# 31_STM32.net
KiCad netlist of a schematic drawn in Altium Designer
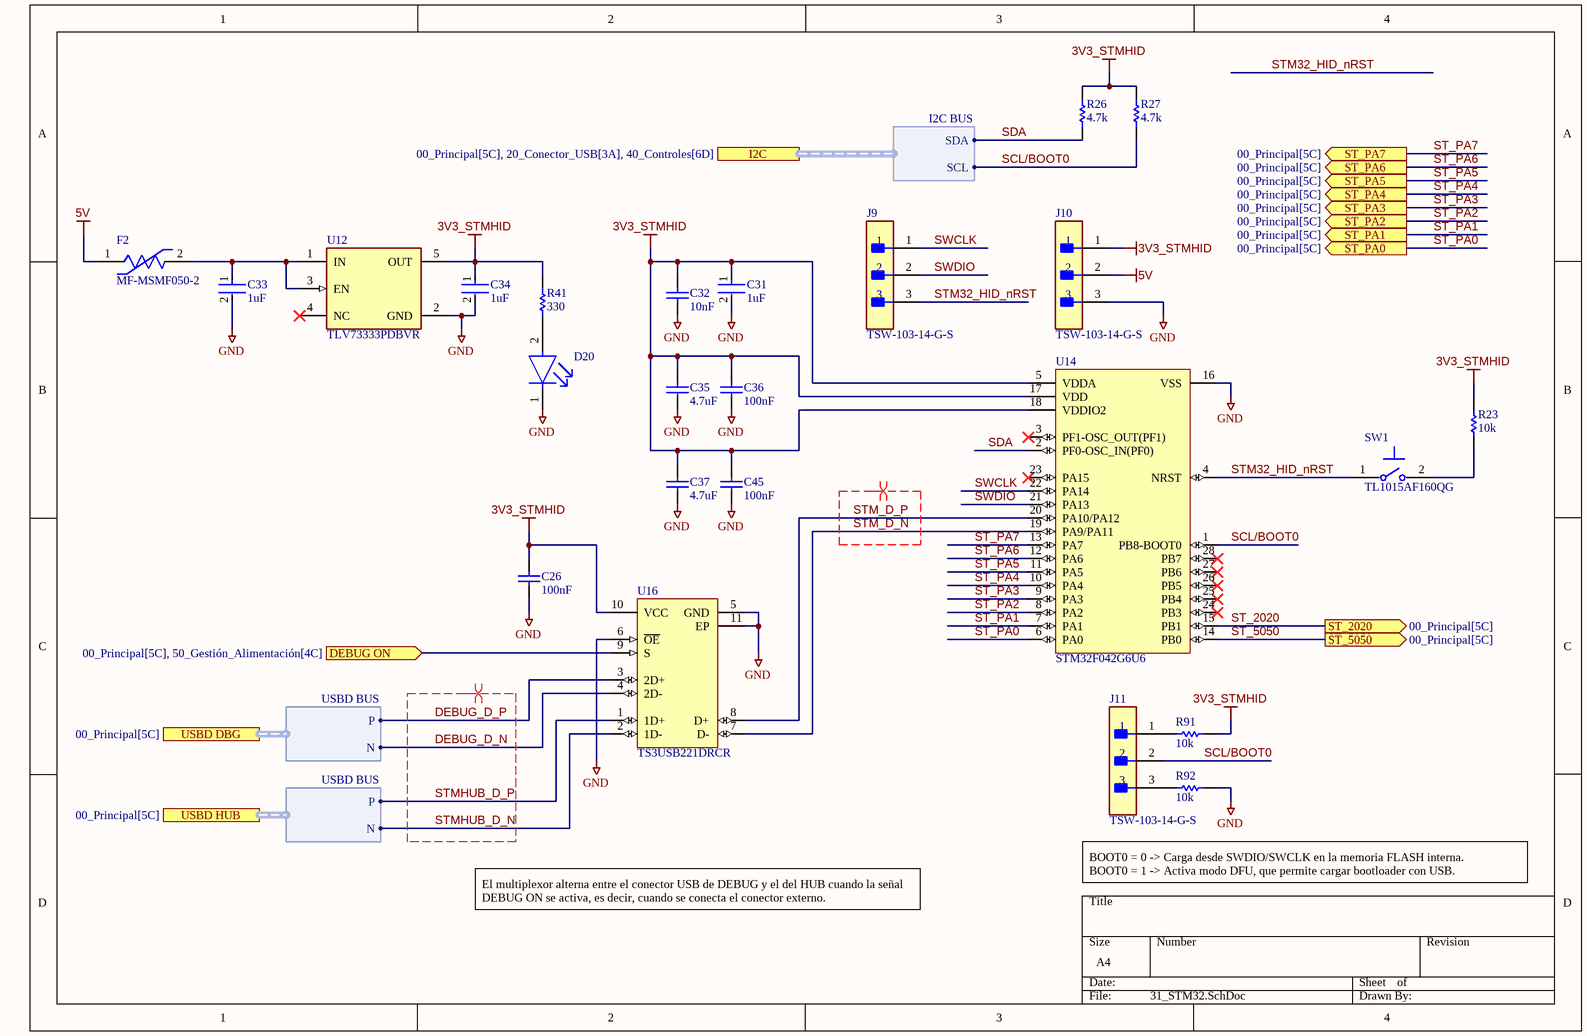
[diagram p0: 31_STM32.SchDoc]

(export (version "E")
  (design (tool "Eeschema 10.0.6"))
  (components
    (comp (ref "C26")
      (value "100nF")
      (footprint "CAPC1005X55X25NL05T05")
      (fields (field (name "MANUFACTURER") "Vitramon") (field (name "PART NUMBER") "VJ0402Y104KXJCW1BC"))
      (libsource (lib "Altium Content Vault") (part "CAP"))
    )
    (comp (ref "C31")
      (value "1uF")
      (footprint "FP-C0402C-BB-IPC_B")
      (description "CAP CER 1UF 16V X5R 0402")
      (fields (field (name "TOLERANCE") "10%"))
      (libsource (lib "Altium Content Vault") (part "b4654b650e69147ec39a6b967a45e02"))
    )
    (comp (ref "C32")
      (value "10nF")
      (footprint "CAPC1005X55X25ML05T05")
      (fields (field (name "PART NUMBER") "VJ0402Y103KXJCW1BC") (field (name "MANUFACTURER") "Vitramon"))
      (libsource (lib "Altium Content Vault") (part "CAP"))
    )
    (comp (ref "C33")
      (value "1uF")
      (footprint "FP-C0402C-BB-IPC_B")
      (description "CAP CER 1UF 16V X5R 0402")
      (fields (field (name "TOLERANCE") "10%"))
      (libsource (lib "Altium Content Vault") (part "b4654b650e69147ec39a6b967a45e02"))
    )
    (comp (ref "C34")
      (value "1uF")
      (footprint "FP-C0402C-BB-IPC_B")
      (description "CAP CER 1UF 16V X5R 0402")
      (fields (field (name "TOLERANCE") "10%"))
      (libsource (lib "Altium Content Vault") (part "b4654b650e69147ec39a6b967a45e02"))
    )
    (comp (ref "C35")
      (value "4.7uF")
      (footprint "CAPC1005X71X25NL10T15")
      (fields
        (field (name "PART NUMBER") "0402ZD475MAT2A")
        (field (name "MANUFACTURER") "AVX Interconnect / Elco")
      )
      (libsource (lib "Altium Content Vault") (part "CAP"))
    )
    (comp (ref "C36")
      (value "100nF")
      (footprint "CAPC1005X55X25NL05T05")
      (fields (field (name "MANUFACTURER") "Vitramon") (field (name "PART NUMBER") "VJ0402Y104KXJCW1BC"))
      (libsource (lib "Altium Content Vault") (part "CAP"))
    )
    (comp (ref "C37")
      (value "4.7uF")
      (footprint "CAPC1005X71X25NL10T15")
      (fields
        (field (name "PART NUMBER") "0402ZD475MAT2A")
        (field (name "MANUFACTURER") "AVX Interconnect / Elco")
      )
      (libsource (lib "Altium Content Vault") (part "CAP"))
    )
    (comp (ref "C45")
      (value "100nF")
      (footprint "CAPC1005X55X25NL05T05")
      (fields (field (name "MANUFACTURER") "Vitramon") (field (name "PART NUMBER") "VJ0402Y104KXJCW1BC"))
      (libsource (lib "Altium Content Vault") (part "CAP"))
    )
    (comp (ref "D20")
      (value "APHD1608LZGCK")
      (footprint "FP-APHD1608LZGCK-MFG")
      (description "LED GREEN CLEAR 1608 SMD")
      (libsource (lib "Altium Content Vault") (part "8706943c75ba83719d021d2fdc84c58"))
    )
    (comp (ref "F2")
      (value "MF-MSMF050-2")
      (footprint "FP-MF-MSMF050-2-MFG")
      (description "PTC RESET FUSE 15V 500MA 1812")
      (fields
        (field (name "MANUFACTURER") "Bourns")
        (field (name "OCTOPART") "https://octopart.com/mf-msmf050-2-bourns-28047")
      )
      (libsource (lib "Altium Content Vault") (part "fc31388045fc42ab786d6d00b506e9f"))
    )
    (comp (ref "J9")
      (value "TSW-103-14-G-S")
      (footprint "FP-TSW-103-14-G-S-MFG")
      (description "CONN HEADER VERT 3POS 2.54MM")
      (libsource (lib "Altium Content Vault") (part "cd3439d6ef35ae5d9b27ec4fdd3e828"))
    )
    (comp (ref "J10")
      (value "TSW-103-14-G-S")
      (footprint "FP-TSW-103-14-G-S-MFG")
      (description "CONN HEADER VERT 3POS 2.54MM")
      (libsource (lib "Altium Content Vault") (part "cd3439d6ef35ae5d9b27ec4fdd3e828"))
    )
    (comp (ref "J11")
      (value "TSW-103-14-G-S")
      (footprint "FP-TSW-103-14-G-S-MFG")
      (description "CONN HEADER VERT 3POS 2.54MM")
      (libsource (lib "Altium Content Vault") (part "cd3439d6ef35ae5d9b27ec4fdd3e828"))
    )
    (comp (ref "R23")
      (value "10k")
      (footprint "RESC1005X40X25ML05T05")
      (fields (field (name "MANUFACTURER") "Panasonic") (field (name "PART NUMBER") "ERJ-2RHD1002X"))
      (libsource (lib "Altium Content Vault") (part "RES"))
    )
    (comp (ref "R26")
      (value "4.7k")
      (footprint "RESC1005X40X25ML05T10")
      (fields (field (name "MANUFACTURER") "Panasonic") (field (name "PART NUMBER") "ERJ-S02F4701X"))
      (libsource (lib "Altium Content Vault") (part "RES"))
    )
    (comp (ref "R27")
      (value "4.7k")
      (footprint "RESC1005X40X25ML05T10")
      (fields (field (name "MANUFACTURER") "Panasonic") (field (name "PART NUMBER") "ERJ-S02F4701X"))
      (libsource (lib "Altium Content Vault") (part "RES"))
    )
    (comp (ref "R41")
      (value "330")
      (footprint "RESC1005X40X25NL10T10")
      (fields (field (name "MANUFACTURER") "Panasonic") (field (name "PART NUMBER") "ERA2AEB331X"))
      (libsource (lib "Altium Content Vault") (part "RES"))
    )
    (comp (ref "R91")
      (value "10k")
      (footprint "RESC1005X40X25ML05T05")
      (fields (field (name "MANUFACTURER") "Panasonic") (field (name "PART NUMBER") "ERJ-2RHD1002X"))
      (libsource (lib "Altium Content Vault") (part "RES"))
    )
    (comp (ref "R92")
      (value "10k")
      (footprint "RESC1005X40X25ML05T05")
      (fields (field (name "MANUFACTURER") "Panasonic") (field (name "PART NUMBER") "ERJ-2RHD1002X"))
      (libsource (lib "Altium Content Vault") (part "RES"))
    )
    (comp (ref "SW1")
      (value "TL1015AF160QG")
      (footprint "FP-TL1015AF160QG-MFG")
      (description "SWITCH TACTILE SPST-NO 0.05A 12V")
      (libsource (lib "Altium Content Vault") (part "2041f8efb62e6aaa548c9fd35e2c2f1"))
    )
    (comp (ref "U12")
      (value "TLV73333PDBVR")
      (footprint "FP-DBV0005A-MFG")
      (description "IC REG LINEAR 3.3V 300MA SOT23-5")
      (fields
        (field (name "MANUFACTURER") "Texas Instruments")
        (field (name "OCTOPART") "https://octopart.com/tlv73333pdbvr-texas+instruments-51080890")
      )
      (libsource (lib "Altium Content Vault") (part "10cdd6a861ce8db355dac0efc8b397e"))
    )
    (comp (ref "U14")
      (value "STM32F042G6U6")
      (footprint "STM-UFQFPN28_V")
      (fields (field (name "MANUFACTURER") "STMicroelectronics"))
      (libsource (lib "Altium Content Vault") (part "MC-ARM-STM32F042-UFQFPN28"))
    )
    (comp (ref "U16")
      (value "TS3USB221DRCR")
      (footprint "DRC0010J_V")
      (fields (field (name "MANUFACTURER") "Texas Instruments"))
      (libsource (lib "Altium Content Vault") (part "TI-TS3USB221-SON_DRC-10"))
    )
  )
  (nets
    (net (code "4") (name "/DEBUG ON") (class "Default")
      (node (ref "U16") (pin "9") (pinfunction "S_9") (pintype "input"))
    )
    (net (code "5") (name "/DEBUG_D_N") (class "Default")
      (node (ref "U16") (pin "4") (pinfunction "2D-_4") (pintype "bidirectional"))
    )
    (net (code "6") (name "/DEBUG_D_P") (class "Default")
      (node (ref "U16") (pin "3") (pinfunction "2D+_3") (pintype "bidirectional"))
    )
    (net (code "7") (name "/SCL{slash}BOOT0") (class "Default")
      (node (ref "J11") (pin "2") (pinfunction "2_2") (pintype "passive"))
      (node (ref "R27") (pin "1") (pinfunction "1_1") (pintype "passive"))
      (node (ref "U14") (pin "1") (pinfunction "PB8-BOOT0_1") (pintype "bidirectional"))
    )
    (net (code "8") (name "/SDA") (class "Default")
      (node (ref "R26") (pin "1") (pinfunction "1_1") (pintype "passive"))
      (node (ref "U14") (pin "2") (pinfunction "PF0-OSC_IN(PF0)_2") (pintype "bidirectional"))
    )
    (net (code "9") (name "/STM32_HID_nRST") (class "Default")
      (node (ref "J9") (pin "3") (pinfunction "3_3") (pintype "passive"))
      (node (ref "SW1") (pin "1") (pinfunction "1_1") (pintype "passive"))
      (node (ref "U14") (pin "4") (pinfunction "NRST_4") (pintype "bidirectional"))
    )
    (net (code "10") (name "/STMHUB_D_N") (class "Default")
      (node (ref "U16") (pin "2") (pinfunction "1D-_2") (pintype "bidirectional"))
    )
    (net (code "11") (name "/STMHUB_D_P") (class "Default")
      (node (ref "U16") (pin "1") (pinfunction "1D+_1") (pintype "bidirectional"))
    )
    (net (code "12") (name "/STM_D_N") (class "Default")
      (node (ref "U14") (pin "19") (pinfunction "PA9/PA11_19") (pintype "bidirectional"))
      (node (ref "U16") (pin "7") (pinfunction "D-_7") (pintype "bidirectional"))
    )
    (net (code "13") (name "/STM_D_P") (class "Default")
      (node (ref "U14") (pin "20") (pinfunction "PA10/PA12_20") (pintype "bidirectional"))
      (node (ref "U16") (pin "8") (pinfunction "D+_8") (pintype "bidirectional"))
    )
    (net (code "14") (name "/ST_2020") (class "Default")
      (node (ref "U14") (pin "15") (pinfunction "PB1_15") (pintype "bidirectional"))
    )
    (net (code "15") (name "/ST_5050") (class "Default")
      (node (ref "U14") (pin "14") (pinfunction "PB0_14") (pintype "bidirectional"))
    )
    (net (code "16") (name "/ST_PA0") (class "Default")
      (node (ref "U14") (pin "6") (pinfunction "PA0_6") (pintype "bidirectional"))
    )
    (net (code "17") (name "/ST_PA1") (class "Default")
      (node (ref "U14") (pin "7") (pinfunction "PA1_7") (pintype "bidirectional"))
    )
    (net (code "18") (name "/ST_PA2") (class "Default")
      (node (ref "U14") (pin "8") (pinfunction "PA2_8") (pintype "bidirectional"))
    )
    (net (code "19") (name "/ST_PA3") (class "Default")
      (node (ref "U14") (pin "9") (pinfunction "PA3_9") (pintype "bidirectional"))
    )
    (net (code "20") (name "/ST_PA4") (class "Default")
      (node (ref "U14") (pin "10") (pinfunction "PA4_10") (pintype "bidirectional"))
    )
    (net (code "21") (name "/ST_PA5") (class "Default")
      (node (ref "U14") (pin "11") (pinfunction "PA5_11") (pintype "bidirectional"))
    )
    (net (code "22") (name "/ST_PA6") (class "Default")
      (node (ref "U14") (pin "12") (pinfunction "PA6_12") (pintype "bidirectional"))
    )
    (net (code "23") (name "/ST_PA7") (class "Default")
      (node (ref "U14") (pin "13") (pinfunction "PA7_13") (pintype "bidirectional"))
    )
    (net (code "24") (name "/SWCLK") (class "Default")
      (node (ref "J9") (pin "1") (pinfunction "1_1") (pintype "passive"))
      (node (ref "U14") (pin "22") (pinfunction "PA14_22") (pintype "bidirectional"))
    )
    (net (code "25") (name "/SWDIO") (class "Default")
      (node (ref "J9") (pin "2") (pinfunction "2_2") (pintype "passive"))
      (node (ref "U14") (pin "21") (pinfunction "PA13_21") (pintype "bidirectional"))
    )
    (net (code "28") (name "3V3_STMHID") (class "Default")
      (node (ref "C26") (pin "2") (pinfunction "2_2") (pintype "passive"))
      (node (ref "C31") (pin "1") (pinfunction "1_1") (pintype "passive"))
      (node (ref "C32") (pin "2") (pinfunction "2_2") (pintype "passive"))
      (node (ref "C34") (pin "1") (pinfunction "1_1") (pintype "passive"))
      (node (ref "C35") (pin "2") (pinfunction "2_2") (pintype "passive"))
      (node (ref "C36") (pin "2") (pinfunction "2_2") (pintype "passive"))
      (node (ref "C37") (pin "2") (pinfunction "2_2") (pintype "passive"))
      (node (ref "C45") (pin "2") (pinfunction "2_2") (pintype "passive"))
      (node (ref "J10") (pin "1") (pinfunction "1_1") (pintype "passive"))
      (node (ref "R23") (pin "2") (pinfunction "2_2") (pintype "passive"))
      (node (ref "R26") (pin "2") (pinfunction "2_2") (pintype "passive"))
      (node (ref "R27") (pin "2") (pinfunction "2_2") (pintype "passive"))
      (node (ref "R41") (pin "2") (pinfunction "2_2") (pintype "passive"))
      (node (ref "R91") (pin "1") (pinfunction "1_1") (pintype "passive"))
      (node (ref "U12") (pin "5") (pinfunction "OUT_5") (pintype "power_in"))
      (node (ref "U14") (pin "17") (pinfunction "VDD_17") (pintype "power_in"))
      (node (ref "U14") (pin "18") (pinfunction "VDDIO2_18") (pintype "power_in"))
      (node (ref "U14") (pin "5") (pinfunction "VDDA_5") (pintype "power_in"))
      (node (ref "U16") (pin "10") (pinfunction "VCC_10") (pintype "power_in"))
    )
    (net (code "29") (name "5V") (class "Default")
      (node (ref "F2") (pin "1") (pinfunction "1_1") (pintype "passive"))
      (node (ref "J10") (pin "2") (pinfunction "2_2") (pintype "passive"))
    )
    (net (code "30") (name "GND") (class "Default")
      (node (ref "C26") (pin "1") (pinfunction "1_1") (pintype "passive"))
      (node (ref "C31") (pin "2") (pinfunction "2_2") (pintype "passive"))
      (node (ref "C32") (pin "1") (pinfunction "1_1") (pintype "passive"))
      (node (ref "C33") (pin "2") (pinfunction "2_2") (pintype "passive"))
      (node (ref "C34") (pin "2") (pinfunction "2_2") (pintype "passive"))
      (node (ref "C35") (pin "1") (pinfunction "1_1") (pintype "passive"))
      (node (ref "C36") (pin "1") (pinfunction "1_1") (pintype "passive"))
      (node (ref "C37") (pin "1") (pinfunction "1_1") (pintype "passive"))
      (node (ref "C45") (pin "1") (pinfunction "1_1") (pintype "passive"))
      (node (ref "D20") (pin "1") (pinfunction "C_1") (pintype "passive"))
      (node (ref "J10") (pin "3") (pinfunction "3_3") (pintype "passive"))
      (node (ref "R92") (pin "1") (pinfunction "1_1") (pintype "passive"))
      (node (ref "U12") (pin "2") (pinfunction "GND_2") (pintype "power_in"))
      (node (ref "U14") (pin "16") (pinfunction "VSS_16") (pintype "power_in"))
      (node (ref "U16") (pin "11") (pinfunction "EP_11") (pintype "passive"))
      (node (ref "U16") (pin "5") (pinfunction "GND_5") (pintype "power_in"))
      (node (ref "U16") (pin "6") (pinfunction "~{OE}_6") (pintype "input"))
    )
    (net (code "31") (name "Net-(D20-A)") (class "Default")
      (node (ref "D20") (pin "2") (pinfunction "A_2") (pintype "passive"))
      (node (ref "R41") (pin "1") (pinfunction "1_1") (pintype "passive"))
    )
    (net (code "32") (name "Net-(J11-Pad1)") (class "Default")
      (node (ref "J11") (pin "1") (pinfunction "1_1") (pintype "passive"))
      (node (ref "R91") (pin "2") (pinfunction "2_2") (pintype "passive"))
    )
    (net (code "33") (name "Net-(J11-Pad3)") (class "Default")
      (node (ref "J11") (pin "3") (pinfunction "3_3") (pintype "passive"))
      (node (ref "R92") (pin "2") (pinfunction "2_2") (pintype "passive"))
    )
    (net (code "34") (name "Net-(R23-Pad1)") (class "Default")
      (node (ref "R23") (pin "1") (pinfunction "1_1") (pintype "passive"))
      (node (ref "SW1") (pin "2") (pinfunction "2_2") (pintype "passive"))
    )
    (net (code "35") (name "Net-(U12-EN)") (class "Default")
      (node (ref "C33") (pin "1") (pinfunction "1_1") (pintype "passive"))
      (node (ref "F2") (pin "2") (pinfunction "2_2") (pintype "passive"))
      (node (ref "U12") (pin "1") (pinfunction "IN_1") (pintype "power_in"))
      (node (ref "U12") (pin "3") (pinfunction "EN_3") (pintype "input"))
    )
    (net (code "36") (name "unconnected-(U12-NC-Pad4)") (class "Default")
      (node (ref "U12") (pin "4") (pinfunction "NC_4") (pintype "passive+no_connect"))
    )
    (net (code "37") (name "unconnected-(U14-PA15-Pad23)") (class "Default")
      (node (ref "U14") (pin "23") (pinfunction "PA15_23") (pintype "bidirectional+no_connect"))
    )
    (net (code "38") (name "unconnected-(U14-PB3-Pad24)") (class "Default")
      (node (ref "U14") (pin "24") (pinfunction "PB3_24") (pintype "bidirectional+no_connect"))
    )
    (net (code "39") (name "unconnected-(U14-PB4-Pad25)") (class "Default")
      (node (ref "U14") (pin "25") (pinfunction "PB4_25") (pintype "bidirectional+no_connect"))
    )
    (net (code "40") (name "unconnected-(U14-PB5-Pad26)") (class "Default")
      (node (ref "U14") (pin "26") (pinfunction "PB5_26") (pintype "bidirectional+no_connect"))
    )
    (net (code "41") (name "unconnected-(U14-PB6-Pad27)") (class "Default")
      (node (ref "U14") (pin "27") (pinfunction "PB6_27") (pintype "bidirectional+no_connect"))
    )
    (net (code "42") (name "unconnected-(U14-PB7-Pad28)") (class "Default")
      (node (ref "U14") (pin "28") (pinfunction "PB7_28") (pintype "bidirectional+no_connect"))
    )
    (net (code "43") (name "unconnected-(U14-PF1-OSC_OUT(PF1)-Pad3)") (class "Default")
      (node (ref "U14") (pin "3") (pinfunction "PF1-OSC_OUT(PF1)_3") (pintype "bidirectional+no_connect"))
    )
  )
)
